# LAB3-1.net
KiCad netlist of a schematic drawn in Altium Designer
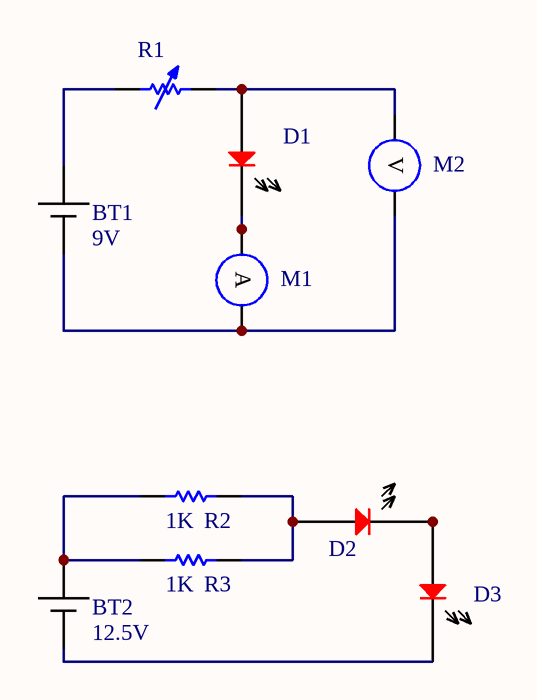
[diagram p0: LAB3-1.SchDoc]

(export (version "E")
  (design (tool "Eeschema 10.0.6"))
  (components
    (comp (ref "BT1")
      (value "9V")
      (description "Generic 1-Cell Power Supply")
      (libsource (lib "SKALE_LIB") (part "GENERIC - 1 CELL BATTERY"))
    )
    (comp (ref "BT2")
      (value "12.5V")
      (description "Generic 1-Cell Power Supply")
      (libsource (lib "SKALE_LIB") (part "GENERIC - 1 CELL BATTERY"))
    )
    (comp (ref "D1")
      (value "LED RED")
      (footprint "150060SS75000")
      (description "Single Color LED, Super Red, Water Clear, 1.1mm")
      (fields
        (field (name "MANUFACTURER") "Wurth Electronics")
        (field (name "MANUFACTURER PART NUMBER") "150060SS75000")
      )
      (libsource (lib "SKALE_LIB") (part "LED RED"))
    )
    (comp (ref "D2")
      (value "LED RED")
      (footprint "150060SS75000")
      (description "Single Color LED, Super Red, Water Clear, 1.1mm")
      (fields
        (field (name "MANUFACTURER") "Wurth Electronics")
        (field (name "MANUFACTURER PART NUMBER") "150060SS75000")
      )
      (libsource (lib "SKALE_LIB") (part "LED RED"))
    )
    (comp (ref "D3")
      (value "LED RED")
      (footprint "150060SS75000")
      (description "Single Color LED, Super Red, Water Clear, 1.1mm")
      (fields
        (field (name "MANUFACTURER") "Wurth Electronics")
        (field (name "MANUFACTURER PART NUMBER") "150060SS75000")
      )
      (libsource (lib "SKALE_LIB") (part "LED RED"))
    )
    (comp (ref "M1")
      (value "?*")
      (description "Generic Ammeter")
      (libsource (lib "SKALE_LIB") (part "GENERIC - AMMETER"))
    )
    (comp (ref "M2")
      (value "GENERIC - VOLTMETER")
      (description "Generic Voltmeter")
      (libsource (lib "SKALE_LIB") (part "GENERIC - VOLTMETER"))
    )
    (comp (ref "R1")
      (value "Res Adj1")
      (footprint "AXIAL-0.7")
      (description "Variable Resistor")
      (fields (field (name "PUBLISHER") "Altium Limited"))
      (libsource (lib "Miscellaneous Devices") (part "Res Adj1"))
    )
    (comp (ref "R2")
      (value "1K")
      (footprint "AXIAL-0.3")
      (description "Resistor")
      (fields (field (name "Comment") "Res1") (field (name "PUBLISHER") "Altium Limited"))
      (libsource (lib "Miscellaneous Devices") (part "Res1"))
    )
    (comp (ref "R3")
      (value "1K")
      (footprint "AXIAL-0.3")
      (description "Resistor")
      (fields (field (name "Comment") "Res1") (field (name "PUBLISHER") "Altium Limited"))
      (libsource (lib "Miscellaneous Devices") (part "Res1"))
    )
  )
  (nets
    (net (code "1") (name "Net-(BT1-+)") (class "Default")
      (node (ref "BT1") (pin "2") (pinfunction "+_2") (pintype "passive"))
      (node (ref "R1") (pin "1") (pinfunction "1_1") (pintype "passive"))
    )
    (net (code "2") (name "Net-(BT1--)") (class "Default")
      (node (ref "BT1") (pin "1") (pinfunction "-_1") (pintype "passive"))
      (node (ref "M1") (pin "2") (pinfunction "2_2") (pintype "passive"))
      (node (ref "M2") (pin "2") (pinfunction "2_2") (pintype "passive"))
    )
    (net (code "3") (name "Net-(BT2-+)") (class "Default")
      (node (ref "BT2") (pin "2") (pinfunction "+_2") (pintype "passive"))
      (node (ref "R2") (pin "1") (pinfunction "1_1") (pintype "passive"))
      (node (ref "R3") (pin "1") (pinfunction "1_1") (pintype "passive"))
    )
    (net (code "4") (name "Net-(BT2--)") (class "Default")
      (node (ref "BT2") (pin "1") (pinfunction "-_1") (pintype "passive"))
      (node (ref "D3") (pin "2") (pinfunction "RED_-_2") (pintype "passive"))
    )
    (net (code "5") (name "Net-(D1-RED_-)") (class "Default")
      (node (ref "D1") (pin "2") (pinfunction "RED_-_2") (pintype "passive"))
      (node (ref "M1") (pin "1") (pinfunction "1_1") (pintype "passive"))
    )
    (net (code "6") (name "Net-(D1-Red_+)") (class "Default")
      (node (ref "D1") (pin "1") (pinfunction "Red_+_1") (pintype "passive"))
      (node (ref "M2") (pin "1") (pinfunction "1_1") (pintype "passive"))
      (node (ref "R1") (pin "2") (pinfunction "2_2") (pintype "passive"))
    )
    (net (code "7") (name "Net-(D2-RED_-)") (class "Default")
      (node (ref "D2") (pin "2") (pinfunction "RED_-_2") (pintype "passive"))
      (node (ref "D3") (pin "1") (pinfunction "Red_+_1") (pintype "passive"))
    )
    (net (code "8") (name "Net-(D2-Red_+)") (class "Default")
      (node (ref "D2") (pin "1") (pinfunction "Red_+_1") (pintype "passive"))
      (node (ref "R2") (pin "2") (pinfunction "2_2") (pintype "passive"))
      (node (ref "R3") (pin "2") (pinfunction "2_2") (pintype "passive"))
    )
  )
)
